# POWER.net
KiCad netlist of a schematic drawn in Altium Designer
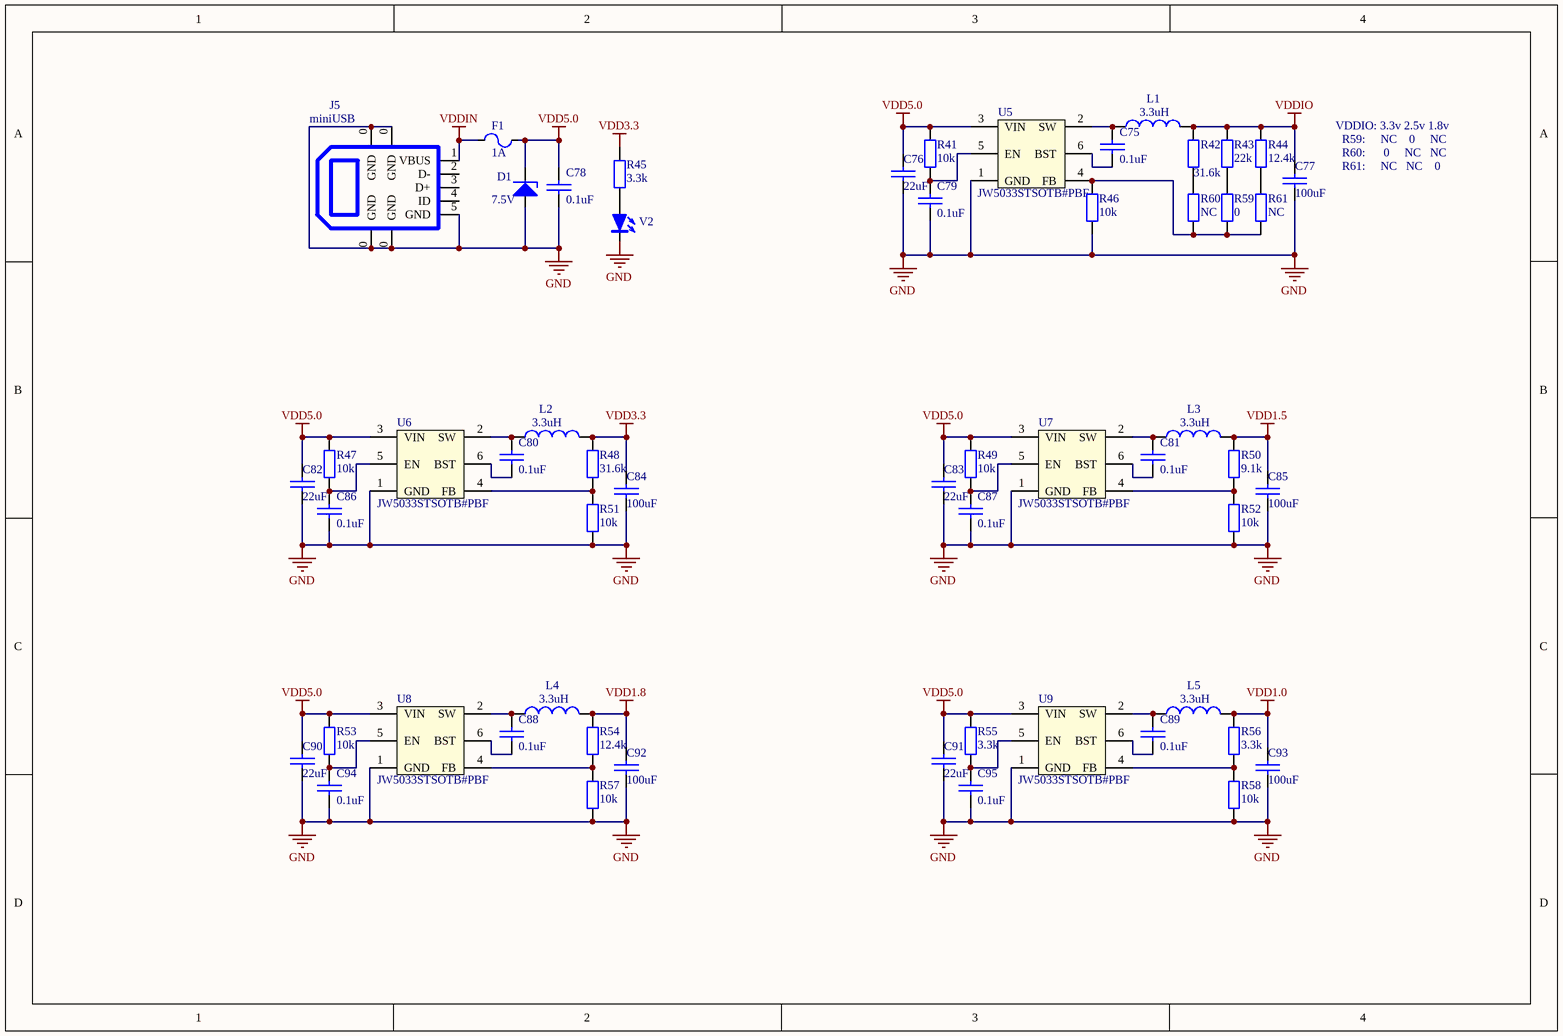
[diagram p0: POWER.SchDoc]

(export (version "E")
  (design (tool "Eeschema 10.0.6"))
  (components
    (comp (ref "C75") (value "0.1uF") (footprint "0402_C_M") (libsource (lib "Component") (part "CAP")))
    (comp (ref "C76") (value "22uF") (footprint "1210_C_M") (libsource (lib "Component") (part "CAP")))
    (comp (ref "C77") (value "100uF") (footprint "1210_C_M") (libsource (lib "Component") (part "CAP")))
    (comp (ref "C78") (value "0.1uF") (footprint "0603_C_M") (libsource (lib "Component") (part "CAP")))
    (comp (ref "C79") (value "0.1uF") (footprint "0402_C_M") (libsource (lib "Component") (part "CAP")))
    (comp (ref "C80") (value "0.1uF") (footprint "0402_C_M") (libsource (lib "Component") (part "CAP")))
    (comp (ref "C81") (value "0.1uF") (footprint "0402_C_M") (libsource (lib "Component") (part "CAP")))
    (comp (ref "C82") (value "22uF") (footprint "1210_C_M") (libsource (lib "Component") (part "CAP")))
    (comp (ref "C83") (value "22uF") (footprint "1210_C_M") (libsource (lib "Component") (part "CAP")))
    (comp (ref "C84") (value "100uF") (footprint "1210_C_M") (libsource (lib "Component") (part "CAP")))
    (comp (ref "C85") (value "100uF") (footprint "1210_C_M") (libsource (lib "Component") (part "CAP")))
    (comp (ref "C86") (value "0.1uF") (footprint "0402_C_M") (libsource (lib "Component") (part "CAP")))
    (comp (ref "C87") (value "0.1uF") (footprint "0402_C_M") (libsource (lib "Component") (part "CAP")))
    (comp (ref "C88") (value "0.1uF") (footprint "0402_C_M") (libsource (lib "Component") (part "CAP")))
    (comp (ref "C89") (value "0.1uF") (footprint "0402_C_M") (libsource (lib "Component") (part "CAP")))
    (comp (ref "C90") (value "22uF") (footprint "1210_C_M") (libsource (lib "Component") (part "CAP")))
    (comp (ref "C91") (value "22uF") (footprint "1210_C_M") (libsource (lib "Component") (part "CAP")))
    (comp (ref "C92") (value "100uF") (footprint "1210_C_M") (libsource (lib "Component") (part "CAP")))
    (comp (ref "C93") (value "100uF") (footprint "1210_C_M") (libsource (lib "Component") (part "CAP")))
    (comp (ref "C94") (value "0.1uF") (footprint "0402_C_M") (libsource (lib "Component") (part "CAP")))
    (comp (ref "C95") (value "0.1uF") (footprint "0402_C_M") (libsource (lib "Component") (part "CAP")))
    (comp (ref "D1") (value "7.5V") (footprint "1206D") (libsource (lib "二极管") (part "D4")))
    (comp (ref "F1") (value "1A") (footprint "1812F") (libsource (lib "常用库") (part "FUSE1")))
    (comp (ref "J5") (value "miniUSB") (footprint "miniUSB") (libsource (lib "Connector") (part "miniUSB")))
    (comp (ref "L1") (value "3.3uH") (footprint "CD42") (libsource (lib "My library") (part "INDUCTOR1")))
    (comp (ref "L2") (value "3.3uH") (footprint "CD42") (libsource (lib "My library") (part "INDUCTOR1")))
    (comp (ref "L3") (value "3.3uH") (footprint "CD42") (libsource (lib "My library") (part "INDUCTOR1")))
    (comp (ref "L4") (value "3.3uH") (footprint "CD42") (libsource (lib "My library") (part "INDUCTOR1")))
    (comp (ref "L5") (value "3.3uH") (footprint "CD42") (libsource (lib "My library") (part "INDUCTOR1")))
    (comp (ref "R41") (value "10k") (footprint "0402_R_M") (libsource (lib "Common") (part "RES2")))
    (comp (ref "R42") (value "31.6k") (footprint "0402_R_M") (libsource (lib "Common") (part "RES2")))
    (comp (ref "R43") (value "22k") (footprint "0402_R_M") (libsource (lib "Common") (part "RES2")))
    (comp (ref "R44") (value "12.4k") (footprint "0402_R_M") (libsource (lib "Common") (part "RES2")))
    (comp (ref "R45") (value "3.3k") (footprint "0402_R_M") (libsource (lib "Common") (part "RES2")))
    (comp (ref "R46") (value "10k") (footprint "0402_R_M") (libsource (lib "Common") (part "RES2")))
    (comp (ref "R47") (value "10k") (footprint "0402_R_M") (libsource (lib "Common") (part "RES2")))
    (comp (ref "R48") (value "31.6k") (footprint "0402_R_M") (libsource (lib "Common") (part "RES2")))
    (comp (ref "R49") (value "10k") (footprint "0402_R_M") (libsource (lib "Common") (part "RES2")))
    (comp (ref "R50") (value "9.1k") (footprint "0402_R_M") (libsource (lib "Common") (part "RES2")))
    (comp (ref "R51") (value "10k") (footprint "0402_R_M") (libsource (lib "Common") (part "RES2")))
    (comp (ref "R52") (value "10k") (footprint "0402_R_M") (libsource (lib "Common") (part "RES2")))
    (comp (ref "R53") (value "10k") (footprint "0402_R_M") (libsource (lib "Common") (part "RES2")))
    (comp (ref "R54") (value "12.4k") (footprint "0402_R_M") (libsource (lib "Common") (part "RES2")))
    (comp (ref "R55") (value "3.3k") (footprint "0402_R_M") (libsource (lib "Common") (part "RES2")))
    (comp (ref "R56") (value "3.3k") (footprint "0402_R_M") (libsource (lib "Common") (part "RES2")))
    (comp (ref "R57") (value "10k") (footprint "0402_R_M") (libsource (lib "Common") (part "RES2")))
    (comp (ref "R58") (value "10k") (footprint "0402_R_M") (libsource (lib "Common") (part "RES2")))
    (comp (ref "R59") (value "0") (footprint "0402_R_M") (libsource (lib "Common") (part "RES2")))
    (comp (ref "R60") (value "NC") (footprint "0402_R_M") (libsource (lib "Common") (part "RES2")))
    (comp (ref "R61") (value "NC") (footprint "0402_R_M") (libsource (lib "Common") (part "RES2")))
    (comp (ref "U5")
      (value "JW5033STSOTB#PBF")
      (footprint "SOT23-6")
      (libsource (lib "XC7A35T") (part "JW5060TTSOTB#PBF"))
    )
    (comp (ref "U6")
      (value "JW5033STSOTB#PBF")
      (footprint "SOT23-6")
      (libsource (lib "XC7A35T") (part "JW5060TTSOTB#PBF"))
    )
    (comp (ref "U7")
      (value "JW5033STSOTB#PBF")
      (footprint "SOT23-6")
      (libsource (lib "XC7A35T") (part "JW5060TTSOTB#PBF"))
    )
    (comp (ref "U8")
      (value "JW5033STSOTB#PBF")
      (footprint "SOT23-6")
      (libsource (lib "XC7A35T") (part "JW5060TTSOTB#PBF"))
    )
    (comp (ref "U9")
      (value "JW5033STSOTB#PBF")
      (footprint "SOT23-6")
      (libsource (lib "XC7A35T") (part "JW5060TTSOTB#PBF"))
    )
    (comp (ref "V2") (value "LED") (footprint "0805D") (libsource (lib "发光管、数码管") (part "LED2")))
  )
  (nets
    (net (code "1") (name "GND") (class "Default")
      (node (ref "C76") (pin "2") (pinfunction "2_2") (pintype "passive"))
      (node (ref "C77") (pin "2") (pinfunction "2_2") (pintype "passive"))
      (node (ref "C78") (pin "2") (pinfunction "2_2") (pintype "passive"))
      (node (ref "C79") (pin "2") (pinfunction "2_2") (pintype "passive"))
      (node (ref "C82") (pin "2") (pinfunction "2_2") (pintype "passive"))
      (node (ref "C83") (pin "2") (pinfunction "2_2") (pintype "passive"))
      (node (ref "C84") (pin "2") (pinfunction "2_2") (pintype "passive"))
      (node (ref "C85") (pin "2") (pinfunction "2_2") (pintype "passive"))
      (node (ref "C86") (pin "2") (pinfunction "2_2") (pintype "passive"))
      (node (ref "C87") (pin "2") (pinfunction "2_2") (pintype "passive"))
      (node (ref "C90") (pin "2") (pinfunction "2_2") (pintype "passive"))
      (node (ref "C91") (pin "2") (pinfunction "2_2") (pintype "passive"))
      (node (ref "C92") (pin "2") (pinfunction "2_2") (pintype "passive"))
      (node (ref "C93") (pin "2") (pinfunction "2_2") (pintype "passive"))
      (node (ref "C94") (pin "2") (pinfunction "2_2") (pintype "passive"))
      (node (ref "C95") (pin "2") (pinfunction "2_2") (pintype "passive"))
      (node (ref "D1") (pin "1") (pinfunction "1_1") (pintype "passive"))
      (node (ref "J5") (pin "0") (pinfunction "GND_0") (pintype "passive"))
      (node (ref "J5") (pin "5") (pinfunction "GND_5") (pintype "passive"))
      (node (ref "R46") (pin "2") (pintype "passive"))
      (node (ref "R51") (pin "2") (pintype "passive"))
      (node (ref "R52") (pin "2") (pintype "passive"))
      (node (ref "R57") (pin "2") (pintype "passive"))
      (node (ref "R58") (pin "2") (pintype "passive"))
      (node (ref "U5") (pin "1") (pinfunction "GND_1") (pintype "passive"))
      (node (ref "U6") (pin "1") (pinfunction "GND_1") (pintype "passive"))
      (node (ref "U7") (pin "1") (pinfunction "GND_1") (pintype "passive"))
      (node (ref "U8") (pin "1") (pinfunction "GND_1") (pintype "passive"))
      (node (ref "U9") (pin "1") (pinfunction "GND_1") (pintype "passive"))
      (node (ref "V2") (pin "2") (pinfunction "2_2") (pintype "passive"))
    )
    (net (code "2") (name "Net-(R42-Pad1)") (class "Default")
      (node (ref "R42") (pin "1") (pintype "passive"))
      (node (ref "R60") (pin "2") (pintype "passive"))
    )
    (net (code "3") (name "Net-(R43-Pad1)") (class "Default")
      (node (ref "R43") (pin "1") (pintype "passive"))
      (node (ref "R59") (pin "2") (pintype "passive"))
    )
    (net (code "4") (name "Net-(R44-Pad1)") (class "Default")
      (node (ref "R44") (pin "1") (pintype "passive"))
      (node (ref "R61") (pin "2") (pintype "passive"))
    )
    (net (code "5") (name "Net-(R45-Pad1)") (class "Default")
      (node (ref "R45") (pin "1") (pintype "passive"))
      (node (ref "V2") (pin "1") (pinfunction "1_1") (pintype "passive"))
    )
    (net (code "6") (name "Net-(U5-BST)") (class "Default")
      (node (ref "C75") (pin "2") (pinfunction "2_2") (pintype "passive"))
      (node (ref "U5") (pin "6") (pinfunction "BST_6") (pintype "passive"))
    )
    (net (code "7") (name "Net-(U5-EN)") (class "Default")
      (node (ref "C79") (pin "1") (pinfunction "1_1") (pintype "passive"))
      (node (ref "R41") (pin "1") (pintype "passive"))
      (node (ref "U5") (pin "5") (pinfunction "EN_5") (pintype "passive"))
    )
    (net (code "8") (name "Net-(U5-FB)") (class "Default")
      (node (ref "R46") (pin "1") (pintype "passive"))
      (node (ref "R59") (pin "1") (pintype "passive"))
      (node (ref "R60") (pin "1") (pintype "passive"))
      (node (ref "R61") (pin "1") (pintype "passive"))
      (node (ref "U5") (pin "4") (pinfunction "FB_4") (pintype "passive"))
    )
    (net (code "9") (name "Net-(U5-SW)") (class "Default")
      (node (ref "C75") (pin "1") (pinfunction "1_1") (pintype "passive"))
      (node (ref "L1") (pin "1") (pinfunction "1_1") (pintype "passive"))
      (node (ref "U5") (pin "2") (pinfunction "SW_2") (pintype "passive"))
    )
    (net (code "10") (name "Net-(U6-BST)") (class "Default")
      (node (ref "C80") (pin "1") (pinfunction "1_1") (pintype "passive"))
      (node (ref "U6") (pin "6") (pinfunction "BST_6") (pintype "passive"))
    )
    (net (code "11") (name "Net-(U6-EN)") (class "Default")
      (node (ref "C86") (pin "1") (pinfunction "1_1") (pintype "passive"))
      (node (ref "R47") (pin "1") (pintype "passive"))
      (node (ref "U6") (pin "5") (pinfunction "EN_5") (pintype "passive"))
    )
    (net (code "12") (name "Net-(U6-FB)") (class "Default")
      (node (ref "R48") (pin "1") (pintype "passive"))
      (node (ref "R51") (pin "1") (pintype "passive"))
      (node (ref "U6") (pin "4") (pinfunction "FB_4") (pintype "passive"))
    )
    (net (code "13") (name "Net-(U6-SW)") (class "Default")
      (node (ref "C80") (pin "2") (pinfunction "2_2") (pintype "passive"))
      (node (ref "L2") (pin "1") (pinfunction "1_1") (pintype "passive"))
      (node (ref "U6") (pin "2") (pinfunction "SW_2") (pintype "passive"))
    )
    (net (code "14") (name "Net-(U7-BST)") (class "Default")
      (node (ref "C81") (pin "1") (pinfunction "1_1") (pintype "passive"))
      (node (ref "U7") (pin "6") (pinfunction "BST_6") (pintype "passive"))
    )
    (net (code "15") (name "Net-(U7-EN)") (class "Default")
      (node (ref "C87") (pin "1") (pinfunction "1_1") (pintype "passive"))
      (node (ref "R49") (pin "1") (pintype "passive"))
      (node (ref "U7") (pin "5") (pinfunction "EN_5") (pintype "passive"))
    )
    (net (code "16") (name "Net-(U7-FB)") (class "Default")
      (node (ref "R50") (pin "1") (pintype "passive"))
      (node (ref "R52") (pin "1") (pintype "passive"))
      (node (ref "U7") (pin "4") (pinfunction "FB_4") (pintype "passive"))
    )
    (net (code "17") (name "Net-(U7-SW)") (class "Default")
      (node (ref "C81") (pin "2") (pinfunction "2_2") (pintype "passive"))
      (node (ref "L3") (pin "1") (pinfunction "1_1") (pintype "passive"))
      (node (ref "U7") (pin "2") (pinfunction "SW_2") (pintype "passive"))
    )
    (net (code "18") (name "Net-(U8-BST)") (class "Default")
      (node (ref "C88") (pin "1") (pinfunction "1_1") (pintype "passive"))
      (node (ref "U8") (pin "6") (pinfunction "BST_6") (pintype "passive"))
    )
    (net (code "19") (name "Net-(U8-EN)") (class "Default")
      (node (ref "C94") (pin "1") (pinfunction "1_1") (pintype "passive"))
      (node (ref "R53") (pin "1") (pintype "passive"))
      (node (ref "U8") (pin "5") (pinfunction "EN_5") (pintype "passive"))
    )
    (net (code "20") (name "Net-(U8-FB)") (class "Default")
      (node (ref "R54") (pin "1") (pintype "passive"))
      (node (ref "R57") (pin "1") (pintype "passive"))
      (node (ref "U8") (pin "4") (pinfunction "FB_4") (pintype "passive"))
    )
    (net (code "21") (name "Net-(U8-SW)") (class "Default")
      (node (ref "C88") (pin "2") (pinfunction "2_2") (pintype "passive"))
      (node (ref "L4") (pin "1") (pinfunction "1_1") (pintype "passive"))
      (node (ref "U8") (pin "2") (pinfunction "SW_2") (pintype "passive"))
    )
    (net (code "22") (name "Net-(U9-BST)") (class "Default")
      (node (ref "C89") (pin "1") (pinfunction "1_1") (pintype "passive"))
      (node (ref "U9") (pin "6") (pinfunction "BST_6") (pintype "passive"))
    )
    (net (code "23") (name "Net-(U9-EN)") (class "Default")
      (node (ref "C95") (pin "1") (pinfunction "1_1") (pintype "passive"))
      (node (ref "R55") (pin "1") (pintype "passive"))
      (node (ref "U9") (pin "5") (pinfunction "EN_5") (pintype "passive"))
    )
    (net (code "24") (name "Net-(U9-FB)") (class "Default")
      (node (ref "R56") (pin "1") (pintype "passive"))
      (node (ref "R58") (pin "1") (pintype "passive"))
      (node (ref "U9") (pin "4") (pinfunction "FB_4") (pintype "passive"))
    )
    (net (code "25") (name "Net-(U9-SW)") (class "Default")
      (node (ref "C89") (pin "2") (pinfunction "2_2") (pintype "passive"))
      (node (ref "L5") (pin "1") (pinfunction "1_1") (pintype "passive"))
      (node (ref "U9") (pin "2") (pinfunction "SW_2") (pintype "passive"))
    )
    (net (code "26") (name "VDD1.0") (class "Default")
      (node (ref "C93") (pin "1") (pinfunction "1_1") (pintype "passive"))
      (node (ref "L5") (pin "2") (pinfunction "2_2") (pintype "passive"))
      (node (ref "R56") (pin "2") (pintype "passive"))
    )
    (net (code "27") (name "VDD1.5") (class "Default")
      (node (ref "C85") (pin "1") (pinfunction "1_1") (pintype "passive"))
      (node (ref "L3") (pin "2") (pinfunction "2_2") (pintype "passive"))
      (node (ref "R50") (pin "2") (pintype "passive"))
    )
    (net (code "28") (name "VDD1.8") (class "Default")
      (node (ref "C92") (pin "1") (pinfunction "1_1") (pintype "passive"))
      (node (ref "L4") (pin "2") (pinfunction "2_2") (pintype "passive"))
      (node (ref "R54") (pin "2") (pintype "passive"))
    )
    (net (code "29") (name "VDD3.3") (class "Default")
      (node (ref "C84") (pin "1") (pinfunction "1_1") (pintype "passive"))
      (node (ref "L2") (pin "2") (pinfunction "2_2") (pintype "passive"))
      (node (ref "R45") (pin "2") (pintype "passive"))
      (node (ref "R48") (pin "2") (pintype "passive"))
    )
    (net (code "30") (name "VDD5.0") (class "Default")
      (node (ref "C76") (pin "1") (pinfunction "1_1") (pintype "passive"))
      (node (ref "C78") (pin "1") (pinfunction "1_1") (pintype "passive"))
      (node (ref "C82") (pin "1") (pinfunction "1_1") (pintype "passive"))
      (node (ref "C83") (pin "1") (pinfunction "1_1") (pintype "passive"))
      (node (ref "C90") (pin "1") (pinfunction "1_1") (pintype "passive"))
      (node (ref "C91") (pin "1") (pinfunction "1_1") (pintype "passive"))
      (node (ref "D1") (pin "2") (pinfunction "2_2") (pintype "passive"))
      (node (ref "F1") (pin "2") (pintype "input"))
      (node (ref "R41") (pin "2") (pintype "passive"))
      (node (ref "R47") (pin "2") (pintype "passive"))
      (node (ref "R49") (pin "2") (pintype "passive"))
      (node (ref "R53") (pin "2") (pintype "passive"))
      (node (ref "R55") (pin "2") (pintype "passive"))
      (node (ref "U5") (pin "3") (pinfunction "VIN_3") (pintype "passive"))
      (node (ref "U6") (pin "3") (pinfunction "VIN_3") (pintype "passive"))
      (node (ref "U7") (pin "3") (pinfunction "VIN_3") (pintype "passive"))
      (node (ref "U8") (pin "3") (pinfunction "VIN_3") (pintype "passive"))
      (node (ref "U9") (pin "3") (pinfunction "VIN_3") (pintype "passive"))
    )
    (net (code "31") (name "VDDIN") (class "Default")
      (node (ref "F1") (pin "1") (pintype "input"))
      (node (ref "J5") (pin "1") (pinfunction "VBUS_1") (pintype "passive"))
    )
    (net (code "32") (name "VDDIO") (class "Default")
      (node (ref "C77") (pin "1") (pinfunction "1_1") (pintype "passive"))
      (node (ref "L1") (pin "2") (pinfunction "2_2") (pintype "passive"))
      (node (ref "R42") (pin "2") (pintype "passive"))
      (node (ref "R43") (pin "2") (pintype "passive"))
      (node (ref "R44") (pin "2") (pintype "passive"))
    )
    (net (code "33") (name "unconnected-(J5-D+-Pad3)") (class "Default")
      (node (ref "J5") (pin "3") (pinfunction "D+_3") (pintype "passive"))
    )
    (net (code "34") (name "unconnected-(J5-D--Pad2)") (class "Default")
      (node (ref "J5") (pin "2") (pinfunction "D-_2") (pintype "passive"))
    )
    (net (code "35") (name "unconnected-(J5-ID-Pad4)") (class "Default")
      (node (ref "J5") (pin "4") (pinfunction "ID_4") (pintype "passive"))
    )
  )
)
